# MelansonTech_PSU_IsolatedShuntAmp_Rev2.net
KiCad netlist of a schematic drawn in Altium Designer
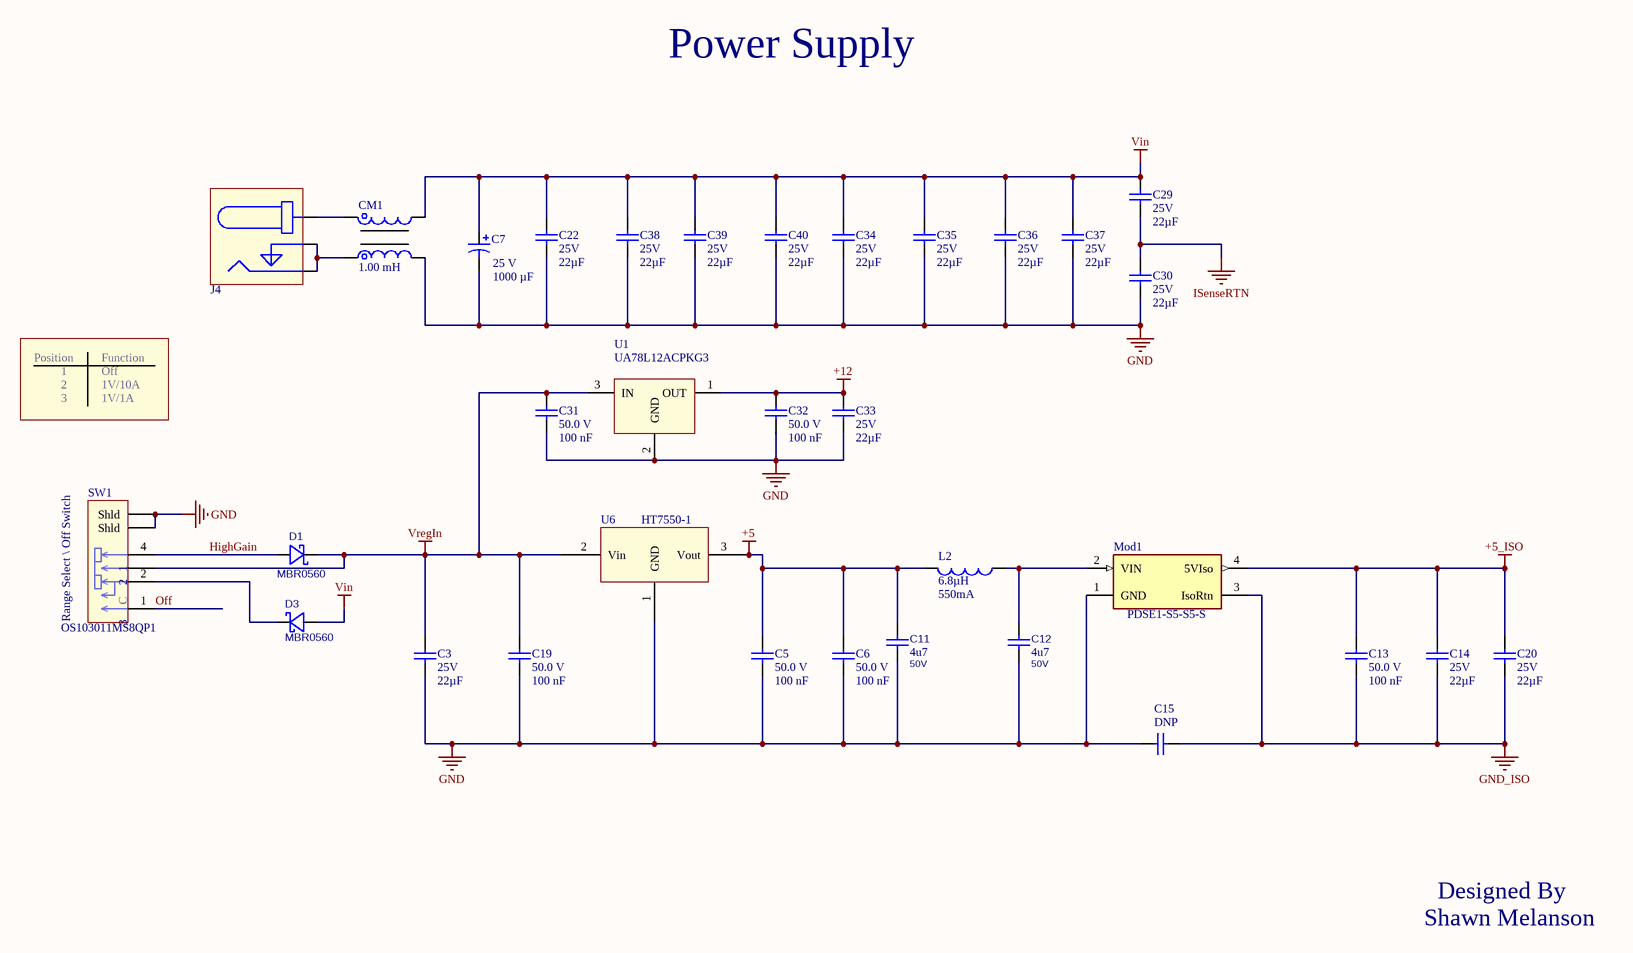
[diagram p0: MelansonTech PSU_IsolatedShuntAmp Rev2.SchDoc]

(export (version "E")
  (design (tool "Eeschema 10.0.6"))
  (components
    (comp (ref "C3")
      (value "CL21A226MAQNNNE")
      (footprint "Cap,0805")
      (description "CAP CER 22UF 25V X5R 0805")
      (fields
        (field (name "MANUFACTURER") "Samsung Electro-Mechanics")
        (field (name "TOLERANCE") "±20%")
        (field (name "VOLTAGE - RATED") "25V")
        (field (name "CAPACITANCE") "22µF")
      )
      (libsource (lib "Master Mar2024") (part "Cap,0805,22uF,25V,X5R,±20%,CL21A226MAQNNNE"))
    )
    (comp (ref "C5")
      (value "CC0805KRX7R9BB104")
      (footprint "CAP, 0805, HD")
      (description "CAP CER 0.1UF 50V X7R 0805")
      (fields
        (field (name "VOLTAGE RATING (DC)") "50.0 V")
        (field (name "CAPACITANCE") "100 nF")
        (field (name "MANUFACTURER") "YAGEO")
      )
      (libsource (lib "Master Mar2024") (part "Cap,0805,100nf,50V,5%,CC0805KRX7R9BB104"))
    )
    (comp (ref "C6")
      (value "CC0805KRX7R9BB104")
      (footprint "CAP, 0805, HD")
      (description "CAP CER 0.1UF 50V X7R 0805")
      (fields
        (field (name "VOLTAGE RATING (DC)") "50.0 V")
        (field (name "CAPACITANCE") "100 nF")
        (field (name "MANUFACTURER") "YAGEO")
      )
      (libsource (lib "Master Mar2024") (part "Cap,0805,100nf,50V,5%,CC0805KRX7R9BB104"))
    )
    (comp (ref "C7")
      (value "A750MV108M1EAAE014")
      (footprint "Cap,5mm Lead Spaceing,14mm HIGH,10MM Dia, Polymer - RA1")
      (description "1000 µF 25 V Aluminum - Polymer Capacitors Radial, Can 14mOhm 2000 Hrs @ 105°C")
      (fields
        (field (name "MANUFACTURER") "KEMET")
        (field (name "CAPACITANCE") "1000 µF")
        (field (name "TOLERANCE") "±20%")
        (field (name "VOLTAGE - RATED") "25 V")
      )
      (libsource (lib "Master Mar2024") (part "Cap,Polar,TH,1000uF,25V,Polymer,±20%,A750MV108M1EAAE014"))
    )
    (comp (ref "C11")
      (value "CL31B475KBHNNNE")
      (footprint "Cap, 1206")
      (description "Cap,SMD,MLCC,4u7,50V,X7R,10%,1206")
      (fields
        (field (name "MANUFACTURER") "Samsung")
        (field (name "TOLERANCE") "10%")
        (field (name "CAPACITANCE") "4u7")
        (field (name "VOLTAGE") "50V")
      )
      (libsource (lib "Master JULY2019") (part "Cap,1206,4.7uF,10%,50V,CL31B475KBHNNNE"))
    )
    (comp (ref "C12")
      (value "CL31B475KBHNNNE")
      (footprint "Cap, 1206")
      (description "Cap,SMD,MLCC,4u7,50V,X7R,10%,1206")
      (fields
        (field (name "MANUFACTURER") "Samsung")
        (field (name "TOLERANCE") "10%")
        (field (name "CAPACITANCE") "4u7")
        (field (name "VOLTAGE") "50V")
      )
      (libsource (lib "Master JULY2019") (part "Cap,1206,4.7uF,10%,50V,CL31B475KBHNNNE"))
    )
    (comp (ref "C13")
      (value "CC0805KRX7R9BB104")
      (footprint "Cap,0805")
      (description "CAP CER 0.1UF 50V X7R 0805")
      (fields
        (field (name "VOLTAGE RATING (DC)") "50.0 V")
        (field (name "CAPACITANCE") "100 nF")
        (field (name "MANUFACTURER") "YAGEO")
      )
      (libsource (lib "Master Mar2024") (part "Cap,0805,100nf,50V,5%,CC0805KRX7R9BB104"))
    )
    (comp (ref "C14")
      (value "CL21A226MAQNNNE")
      (footprint "Cap,0805")
      (description "CAP CER 22UF 25V X5R 0805")
      (fields
        (field (name "MANUFACTURER") "Samsung Electro-Mechanics")
        (field (name "TOLERANCE") "±20%")
        (field (name "VOLTAGE - RATED") "25V")
        (field (name "CAPACITANCE") "22µF")
      )
      (libsource (lib "Master Mar2024") (part "Cap,0805,22uF,25V,X5R,±20%,CL21A226MAQNNNE"))
    )
    (comp (ref "C15")
      (value "S102K33Y5PP63K5R")
      (footprint "Cap, 5mm Lead Spaceing, 4mm dai")
      (description "CAP CER 1000PF 2KV Y5P RADIAL")
      (fields (field (name "MANUFACTURER") "Vishay BC Components") (field (name "TOLERANCE") "±10%"))
      (libsource (lib "Master JULY2019") (part "Cap,TH,Ceramic,5mm Spacing,1nF,2kV, S102K33Y5PP63K5R"))
    )
    (comp (ref "C19")
      (value "CC0805KRX7R9BB104")
      (footprint "CAP, 0805, HD")
      (description "CAP CER 0.1UF 50V X7R 0805")
      (fields
        (field (name "VOLTAGE RATING (DC)") "50.0 V")
        (field (name "CAPACITANCE") "100 nF")
        (field (name "MANUFACTURER") "YAGEO")
      )
      (libsource (lib "Master Mar2024") (part "Cap,0805,100nf,50V,5%,CC0805KRX7R9BB104"))
    )
    (comp (ref "C20")
      (value "CL21A226MAQNNNE")
      (footprint "Cap,0805")
      (description "CAP CER 22UF 25V X5R 0805")
      (fields
        (field (name "MANUFACTURER") "Samsung Electro-Mechanics")
        (field (name "TOLERANCE") "±20%")
        (field (name "VOLTAGE - RATED") "25V")
        (field (name "CAPACITANCE") "22µF")
      )
      (libsource (lib "Master Mar2024") (part "Cap,0805,22uF,25V,X5R,±20%,CL21A226MAQNNNE"))
    )
    (comp (ref "C22")
      (value "CL21A226MAQNNNE")
      (footprint "Cap,0805")
      (description "CAP CER 22UF 25V X5R 0805")
      (fields
        (field (name "MANUFACTURER") "Samsung Electro-Mechanics")
        (field (name "TOLERANCE") "±20%")
        (field (name "VOLTAGE - RATED") "25V")
        (field (name "CAPACITANCE") "22µF")
      )
      (libsource (lib "Master Mar2024") (part "Cap,0805,22uF,25V,X5R,±20%,CL21A226MAQNNNE"))
    )
    (comp (ref "C29")
      (value "CL21A226MAQNNNE")
      (footprint "Cap,0805")
      (description "CAP CER 22UF 25V X5R 0805")
      (fields
        (field (name "MANUFACTURER") "Samsung Electro-Mechanics")
        (field (name "TOLERANCE") "±20%")
        (field (name "VOLTAGE - RATED") "25V")
        (field (name "CAPACITANCE") "22µF")
      )
      (libsource (lib "Master Mar2024") (part "Cap,0805,22uF,25V,X5R,±20%,CL21A226MAQNNNE"))
    )
    (comp (ref "C30")
      (value "CL21A226MAQNNNE")
      (footprint "Cap,0805")
      (description "CAP CER 22UF 25V X5R 0805")
      (fields
        (field (name "MANUFACTURER") "Samsung Electro-Mechanics")
        (field (name "TOLERANCE") "±20%")
        (field (name "VOLTAGE - RATED") "25V")
        (field (name "CAPACITANCE") "22µF")
      )
      (libsource (lib "Master Mar2024") (part "Cap,0805,22uF,25V,X5R,±20%,CL21A226MAQNNNE"))
    )
    (comp (ref "C31")
      (value "CC0805KRX7R9BB104")
      (footprint "CAP, 0805, HD")
      (description "CAP CER 0.1UF 50V X7R 0805")
      (fields
        (field (name "VOLTAGE RATING (DC)") "50.0 V")
        (field (name "CAPACITANCE") "100 nF")
        (field (name "MANUFACTURER") "YAGEO")
      )
      (libsource (lib "Master Mar2024") (part "Cap,0805,100nf,50V,5%,CC0805KRX7R9BB104"))
    )
    (comp (ref "C32")
      (value "CC0805KRX7R9BB104")
      (footprint "CAP, 0805, HD")
      (description "CAP CER 0.1UF 50V X7R 0805")
      (fields
        (field (name "VOLTAGE RATING (DC)") "50.0 V")
        (field (name "CAPACITANCE") "100 nF")
        (field (name "MANUFACTURER") "YAGEO")
      )
      (libsource (lib "Master Mar2024") (part "Cap,0805,100nf,50V,5%,CC0805KRX7R9BB104"))
    )
    (comp (ref "C33")
      (value "CL21A226MAQNNNE")
      (footprint "Cap,0805")
      (description "CAP CER 22UF 25V X5R 0805")
      (fields
        (field (name "MANUFACTURER") "Samsung Electro-Mechanics")
        (field (name "TOLERANCE") "±20%")
        (field (name "VOLTAGE - RATED") "25V")
        (field (name "CAPACITANCE") "22µF")
      )
      (libsource (lib "Master Mar2024") (part "Cap,0805,22uF,25V,X5R,±20%,CL21A226MAQNNNE"))
    )
    (comp (ref "C34")
      (value "CL21A226MAQNNNE")
      (footprint "Cap,0805")
      (description "CAP CER 22UF 25V X5R 0805")
      (fields
        (field (name "MANUFACTURER") "Samsung Electro-Mechanics")
        (field (name "TOLERANCE") "±20%")
        (field (name "VOLTAGE - RATED") "25V")
        (field (name "CAPACITANCE") "22µF")
      )
      (libsource (lib "Master Mar2024") (part "Cap,0805,22uF,25V,X5R,±20%,CL21A226MAQNNNE"))
    )
    (comp (ref "C35")
      (value "CL21A226MAQNNNE")
      (footprint "Cap,0805")
      (description "CAP CER 22UF 25V X5R 0805")
      (fields
        (field (name "MANUFACTURER") "Samsung Electro-Mechanics")
        (field (name "TOLERANCE") "±20%")
        (field (name "VOLTAGE - RATED") "25V")
        (field (name "CAPACITANCE") "22µF")
      )
      (libsource (lib "Master Mar2024") (part "Cap,0805,22uF,25V,X5R,±20%,CL21A226MAQNNNE"))
    )
    (comp (ref "C36")
      (value "CL21A226MAQNNNE")
      (footprint "Cap,0805")
      (description "CAP CER 22UF 25V X5R 0805")
      (fields
        (field (name "MANUFACTURER") "Samsung Electro-Mechanics")
        (field (name "TOLERANCE") "±20%")
        (field (name "VOLTAGE - RATED") "25V")
        (field (name "CAPACITANCE") "22µF")
      )
      (libsource (lib "Master Mar2024") (part "Cap,0805,22uF,25V,X5R,±20%,CL21A226MAQNNNE"))
    )
    (comp (ref "C37")
      (value "CL21A226MAQNNNE")
      (footprint "Cap,0805")
      (description "CAP CER 22UF 25V X5R 0805")
      (fields
        (field (name "MANUFACTURER") "Samsung Electro-Mechanics")
        (field (name "TOLERANCE") "±20%")
        (field (name "VOLTAGE - RATED") "25V")
        (field (name "CAPACITANCE") "22µF")
      )
      (libsource (lib "Master Mar2024") (part "Cap,0805,22uF,25V,X5R,±20%,CL21A226MAQNNNE"))
    )
    (comp (ref "C38")
      (value "CL21A226MAQNNNE")
      (footprint "Cap,0805")
      (description "CAP CER 22UF 25V X5R 0805")
      (fields
        (field (name "MANUFACTURER") "Samsung Electro-Mechanics")
        (field (name "TOLERANCE") "±20%")
        (field (name "VOLTAGE - RATED") "25V")
        (field (name "CAPACITANCE") "22µF")
      )
      (libsource (lib "Master Mar2024") (part "Cap,0805,22uF,25V,X5R,±20%,CL21A226MAQNNNE"))
    )
    (comp (ref "C39")
      (value "CL21A226MAQNNNE")
      (footprint "Cap,0805")
      (description "CAP CER 22UF 25V X5R 0805")
      (fields
        (field (name "MANUFACTURER") "Samsung Electro-Mechanics")
        (field (name "TOLERANCE") "±20%")
        (field (name "VOLTAGE - RATED") "25V")
        (field (name "CAPACITANCE") "22µF")
      )
      (libsource (lib "Master Mar2024") (part "Cap,0805,22uF,25V,X5R,±20%,CL21A226MAQNNNE"))
    )
    (comp (ref "C40")
      (value "CL21A226MAQNNNE")
      (footprint "Cap,0805")
      (description "CAP CER 22UF 25V X5R 0805")
      (fields
        (field (name "MANUFACTURER") "Samsung Electro-Mechanics")
        (field (name "TOLERANCE") "±20%")
        (field (name "VOLTAGE - RATED") "25V")
        (field (name "CAPACITANCE") "22µF")
      )
      (libsource (lib "Master Mar2024") (part "Cap,0805,22uF,25V,X5R,±20%,CL21A226MAQNNNE"))
    )
    (comp (ref "CM1")
      (value "DR331-105BE")
      (footprint "CM Choke,SMD, DR331")
      (description "CMC 1MH 500MA 2LN SMD")
      (fields (field (name "INDUCTANCE") "1.00 mH"))
      (libsource (lib "Master Mar2024") (part "common mode, 1mH@100kHz, 500mA, SMD,2ln, DR331-105BE"))
    )
    (comp (ref "D1")
      (value "MBR0560")
      (footprint "SOD123")
      (description "Dio,Sig,Schtky,0.5A,60V,SOD123")
      (fields (field (name "MANUFACTURER") "MCC") (field (name "VOLTAGE") "60V"))
      (libsource (lib "Master DEC 2020") (part "Diode,SOD123,Shottky,60V,0.5A,MBR0560"))
    )
    (comp (ref "D3")
      (value "MBR0560")
      (footprint "SOD123")
      (description "Dio,Sig,Schtky,0.5A,60V,SOD123")
      (fields (field (name "MANUFACTURER") "MCC") (field (name "VOLTAGE") "60V"))
      (libsource (lib "Master DEC 2020") (part "Diode,SOD123,Shottky,60V,0.5A,MBR0560"))
    )
    (comp (ref "J4")
      (value "PJ-002A")
      (footprint "Connector,Barrel,2.1mm,5.5mm,DC power Jack")
      (description "Power Barrel Connector Jack 2.10mm ID (0.083\"), 5.50mm OD (0.217\") Through Hole, Right Angle")
      (fields (field (name "MANUFACTURER") "CUI Inc."))
      (libsource (lib "Master Nov2021") (part "Connector,Barrel,ID 2.1mm,OD 5.5mm,Power Connect, PJ-002A"))
    )
    (comp (ref "L2")
      (value "MLZ2012N6R8LT000")
      (footprint "Ind, 0805")
      (description "FIXED IND 6.8UH 550MA 250 MOHM")
      (fields
        (field (name "MANUFACTURER") "TDK Corporation")
        (field (name "TOLERANCE") "±20%")
        (field (name "INDUCTANCE") "6.8µH")
        (field (name "CURRENT RATING (AMPS)") "550mA")
      )
      (libsource (lib "Master JULY2019") (part "Ind,0805,6.8uH,550mA,0.25Ω, MLZ2012N6R8LT000"))
    )
    (comp (ref "Mod1")
      (value "PDSE1-S5-S5-S")
      (footprint "CONV_PDSE1-S5-S5-S")
      (description "DC-DC ISOLATED, 1 W, 4.5-5.5 VDC")
      (fields (field (name "MANUFACTURER") "CUI Inc."))
      (libsource (lib "Master JULY2019") (part "Mod,PSU,4.5-5.5Vin,5Vout,1W, PDSE1-S5-S5-S"))
    )
    (comp (ref "SW1")
      (value "OS103011MS8QP1")
      (footprint "Switch,Slide,.SP3T, OS103011 -Side")
      (description "SWITCH SLIDE SP3T 100MA 12V")
      (fields (field (name "MANUFACTURER") "C&K"))
      (libsource (lib "Master Nov2021") (part "Switch,TH,Slide,SP3T,100MA,12V,OS103011MS8QP1"))
    )
    (comp (ref "U1")
      (value "UA78L12ACPKG3")
      (footprint "SOT89-3")
      (description "IC REG LINEAR 12V 100MA SOT89-3")
      (fields (field (name "MANUFACTURER") "Texas Instruments"))
      (libsource (lib "Master Nov2021") (part "Reg,Linear,Pos,Fixed,12Vout,27Vin,100mA,UA78L12ACPKG3"))
    )
    (comp (ref "U6")
      (value "HT7550-1")
      (footprint "SOT89-3")
      (description "LOW DROPOUT REGULATORS(LDO) POSITIVE FIXED 55MV @ 1MA 30V 5V 150MA SOT-89(SOT-89-3) ROHS")
      (fields
        (field (name "LCSC PART #") "C16106")
        (field (name "MANUFACTURER") "Holtek Semicon")
        (field (name "MFG P/N") "HT7550-1")
      )
      (libsource (lib "Master DEC 2020") (part "Reg,Linear,Fixed,SOT-89-3,30Vin,5Vout,150mA,HT7550-1"))
    )
  )
  (nets
    (net (code "1") (name "+5") (class "Default")
      (node (ref "C11") (pin "2") (pintype "passive"))
      (node (ref "C5") (pin "2") (pinfunction "2_2") (pintype "passive"))
      (node (ref "C6") (pin "2") (pinfunction "2_2") (pintype "passive"))
      (node (ref "L2") (pin "2") (pinfunction "2_2") (pintype "passive"))
      (node (ref "U6") (pin "3") (pinfunction "Vout_3") (pintype "passive"))
    )
    (net (code "2") (name "+5_ISO") (class "Default")
      (node (ref "C13") (pin "2") (pinfunction "2_2") (pintype "passive"))
      (node (ref "C14") (pin "2") (pinfunction "2_2") (pintype "passive"))
      (node (ref "C20") (pin "2") (pinfunction "2_2") (pintype "passive"))
      (node (ref "Mod1") (pin "4") (pinfunction "5VIso_4") (pintype "output"))
    )
    (net (code "3") (name "+12") (class "Default")
      (node (ref "C32") (pin "2") (pinfunction "2_2") (pintype "passive"))
      (node (ref "C33") (pin "2") (pinfunction "2_2") (pintype "passive"))
      (node (ref "U1") (pin "1") (pinfunction "OUT_1") (pintype "passive"))
    )
    (net (code "4") (name "/HighGain") (class "Default")
      (node (ref "D1") (pin "2") (pinfunction "A_2") (pintype "passive"))
      (node (ref "SW1") (pin "4") (pinfunction "4_4") (pintype "passive"))
    )
    (net (code "5") (name "/Off") (class "Default")
      (node (ref "SW1") (pin "1") (pinfunction "1_1") (pintype "passive"))
    )
    (net (code "6") (name "GND") (class "Default")
      (node (ref "C11") (pin "1") (pintype "passive"))
      (node (ref "C12") (pin "1") (pintype "passive"))
      (node (ref "C15") (pin "2") (pinfunction "2_2") (pintype "passive"))
      (node (ref "C19") (pin "1") (pinfunction "1_1") (pintype "passive"))
      (node (ref "C22") (pin "1") (pinfunction "1_1") (pintype "passive"))
      (node (ref "C3") (pin "1") (pinfunction "1_1") (pintype "passive"))
      (node (ref "C30") (pin "1") (pinfunction "1_1") (pintype "passive"))
      (node (ref "C31") (pin "1") (pinfunction "1_1") (pintype "passive"))
      (node (ref "C32") (pin "1") (pinfunction "1_1") (pintype "passive"))
      (node (ref "C33") (pin "1") (pinfunction "1_1") (pintype "passive"))
      (node (ref "C34") (pin "1") (pinfunction "1_1") (pintype "passive"))
      (node (ref "C35") (pin "1") (pinfunction "1_1") (pintype "passive"))
      (node (ref "C36") (pin "1") (pinfunction "1_1") (pintype "passive"))
      (node (ref "C37") (pin "1") (pinfunction "1_1") (pintype "passive"))
      (node (ref "C38") (pin "1") (pinfunction "1_1") (pintype "passive"))
      (node (ref "C39") (pin "1") (pinfunction "1_1") (pintype "passive"))
      (node (ref "C40") (pin "1") (pinfunction "1_1") (pintype "passive"))
      (node (ref "C5") (pin "1") (pinfunction "1_1") (pintype "passive"))
      (node (ref "C6") (pin "1") (pinfunction "1_1") (pintype "passive"))
      (node (ref "C7") (pin "2") (pinfunction "2_2") (pintype "passive"))
      (node (ref "CM1") (pin "4") (pinfunction "4_4") (pintype "passive"))
      (node (ref "Mod1") (pin "1") (pinfunction "GND_1") (pintype "power_in"))
      (node (ref "SW1") (pin "5") (pinfunction "Shld_5") (pintype "passive"))
      (node (ref "SW1") (pin "6") (pinfunction "Shld_6") (pintype "passive"))
      (node (ref "U1") (pin "2") (pinfunction "GND_2") (pintype "passive"))
      (node (ref "U6") (pin "1") (pinfunction "GND_1") (pintype "passive"))
    )
    (net (code "7") (name "GND_ISO") (class "Default")
      (node (ref "C13") (pin "1") (pinfunction "1_1") (pintype "passive"))
      (node (ref "C14") (pin "1") (pinfunction "1_1") (pintype "passive"))
      (node (ref "C15") (pin "1") (pinfunction "1_1") (pintype "passive"))
      (node (ref "C20") (pin "1") (pinfunction "1_1") (pintype "passive"))
      (node (ref "Mod1") (pin "3") (pinfunction "IsoRtn_3") (pintype "power_in"))
    )
    (net (code "8") (name "ISenseRTN") (class "Default")
      (node (ref "C29") (pin "1") (pinfunction "1_1") (pintype "passive"))
      (node (ref "C30") (pin "2") (pinfunction "2_2") (pintype "passive"))
    )
    (net (code "9") (name "Net-(CM1-Pad1)") (class "Default")
      (node (ref "CM1") (pin "1") (pinfunction "1_1") (pintype "passive"))
      (node (ref "J4") (pin "1") (pinfunction "1_1") (pintype "passive"))
    )
    (net (code "10") (name "Net-(CM1-Pad3)") (class "Default")
      (node (ref "CM1") (pin "3") (pinfunction "3_3") (pintype "passive"))
      (node (ref "J4") (pin "2") (pinfunction "2_2") (pintype "passive"))
      (node (ref "J4") (pin "3") (pinfunction "3_3") (pintype "passive"))
    )
    (net (code "11") (name "Net-(D3-C)") (class "Default")
      (node (ref "D3") (pin "1") (pinfunction "C_1") (pintype "passive"))
      (node (ref "SW1") (pin "2") (pinfunction "2_2") (pintype "passive"))
    )
    (net (code "12") (name "Net-(Mod1-VIN)") (class "Default")
      (node (ref "C12") (pin "2") (pintype "passive"))
      (node (ref "L2") (pin "1") (pinfunction "1_1") (pintype "passive"))
      (node (ref "Mod1") (pin "2") (pinfunction "VIN_2") (pintype "input"))
    )
    (net (code "13") (name "Vin") (class "Default")
      (node (ref "C22") (pin "2") (pinfunction "2_2") (pintype "passive"))
      (node (ref "C29") (pin "2") (pinfunction "2_2") (pintype "passive"))
      (node (ref "C34") (pin "2") (pinfunction "2_2") (pintype "passive"))
      (node (ref "C35") (pin "2") (pinfunction "2_2") (pintype "passive"))
      (node (ref "C36") (pin "2") (pinfunction "2_2") (pintype "passive"))
      (node (ref "C37") (pin "2") (pinfunction "2_2") (pintype "passive"))
      (node (ref "C38") (pin "2") (pinfunction "2_2") (pintype "passive"))
      (node (ref "C39") (pin "2") (pinfunction "2_2") (pintype "passive"))
      (node (ref "C40") (pin "2") (pinfunction "2_2") (pintype "passive"))
      (node (ref "C7") (pin "1") (pinfunction "1_1") (pintype "passive"))
      (node (ref "CM1") (pin "2") (pinfunction "2_2") (pintype "passive"))
      (node (ref "D3") (pin "2") (pinfunction "A_2") (pintype "passive"))
    )
    (net (code "14") (name "VregIn") (class "Default")
      (node (ref "C19") (pin "2") (pinfunction "2_2") (pintype "passive"))
      (node (ref "C3") (pin "2") (pinfunction "2_2") (pintype "passive"))
      (node (ref "C31") (pin "2") (pinfunction "2_2") (pintype "passive"))
      (node (ref "D1") (pin "1") (pinfunction "C_1") (pintype "passive"))
      (node (ref "SW1") (pin "3") (pinfunction "3_3") (pintype "passive"))
      (node (ref "U1") (pin "3") (pinfunction "IN_3") (pintype "passive"))
      (node (ref "U6") (pin "2") (pinfunction "Vin_2") (pintype "passive"))
    )
  )
)
